# ArmRobot.net
KiCad netlist of a schematic drawn in EAGLE
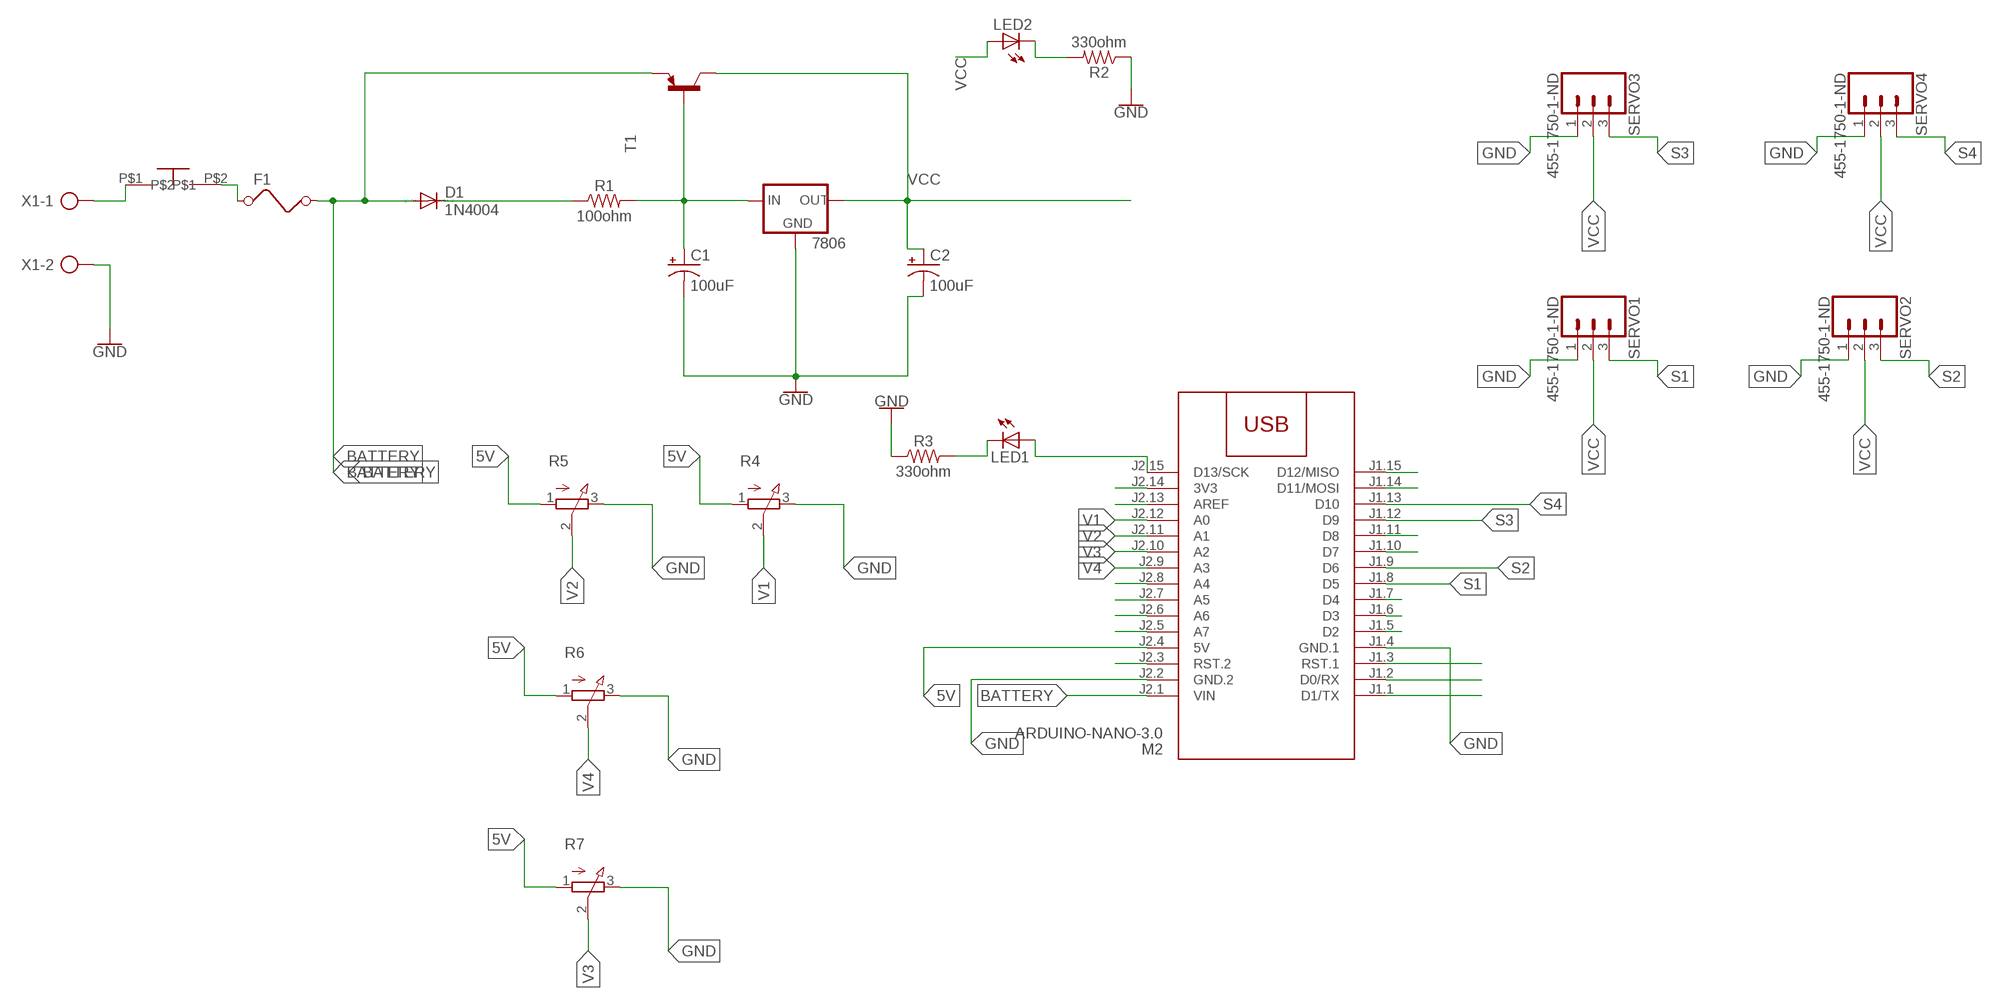
[diagram p0: schematic, sheet 1]

(export (version "E")
  (design (tool "Eeschema 10.0.6"))
  (components
    (comp (ref "7806")
      (value "78XXS")
      (footprint "eagle-import:78XXS")
      (libsource (lib "eagle-import") (part "78XXS"))
    )
    (comp (ref "C1")
      (value "100uF")
      (footprint "eagle-import:CPOL-RADIAL-2.5MM-6.5MM")
      (libsource (lib "eagle-import") (part "100UF-POLAR-RADIAL-2.5MM-25V-20%"))
    )
    (comp (ref "C2")
      (value "100uF")
      (footprint "eagle-import:CPOL-RADIAL-2.5MM-6.5MM")
      (libsource (lib "eagle-import") (part "100UF-POLAR-RADIAL-2.5MM-25V-20%"))
    )
    (comp (ref "D1")
      (value "1N4004")
      (footprint "eagle-import:DO41-10")
      (libsource (lib "eagle-import") (part "1N4004"))
    )
    (comp (ref "F1")
      (value "FUSE")
      (footprint "eagle-import:FUSE")
      (libsource (lib "eagle-import") (part "FUSE"))
    )
    (comp (ref "LED1")
      (value "LED3MM")
      (footprint "eagle-import:LED3MM")
      (libsource (lib "eagle-import") (part "LED3MM"))
    )
    (comp (ref "LED2")
      (value "LED3MM")
      (footprint "eagle-import:LED3MM")
      (libsource (lib "eagle-import") (part "LED3MM"))
    )
    (comp (ref "M2")
      (value "ARDUINO-NANO-3.0")
      (footprint "eagle-import:ARDUINO-NANO-3.0")
      (libsource (lib "eagle-import") (part "ARDUINO-NANO-3.0"))
    )
    (comp (ref "R1")
      (value "100ohm")
      (footprint "eagle-import:AXIAL-0.3")
      (libsource (lib "eagle-import") (part "10MOHM-HORIZ-1/4W-5%"))
    )
    (comp (ref "R2")
      (value "330ohm")
      (footprint "eagle-import:AXIAL-0.3")
      (libsource (lib "eagle-import") (part "10MOHM-HORIZ-1/4W-5%"))
    )
    (comp (ref "R3")
      (value "330ohm")
      (footprint "eagle-import:AXIAL-0.3")
      (libsource (lib "eagle-import") (part "10MOHM-HORIZ-1/4W-5%"))
    )
    (comp (ref "R4")
      (value "3RP/1610N")
      (footprint "eagle-import:3RP_1610N")
      (libsource (lib "eagle-import") (part "3RP/1610N"))
    )
    (comp (ref "R5")
      (value "3RP/1610N")
      (footprint "eagle-import:3RP_1610N")
      (libsource (lib "eagle-import") (part "3RP/1610N"))
    )
    (comp (ref "R6")
      (value "3RP/1610N")
      (footprint "eagle-import:3RP_1610N")
      (libsource (lib "eagle-import") (part "3RP/1610N"))
    )
    (comp (ref "R7")
      (value "3RP/1610N")
      (footprint "eagle-import:3RP_1610N")
      (libsource (lib "eagle-import") (part "3RP/1610N"))
    )
    (comp (ref "SERVO1")
      (value "455-1750-1-ND")
      (footprint "eagle-import:1X03")
      (libsource (lib "eagle-import") (part "CONN_03"))
    )
    (comp (ref "SERVO2")
      (value "455-1750-1-ND")
      (footprint "eagle-import:1X03")
      (libsource (lib "eagle-import") (part "CONN_03"))
    )
    (comp (ref "SERVO3")
      (value "455-1750-1-ND")
      (footprint "eagle-import:1X03")
      (libsource (lib "eagle-import") (part "CONN_03"))
    )
    (comp (ref "SERVO4")
      (value "455-1750-1-ND")
      (footprint "eagle-import:1X03")
      (libsource (lib "eagle-import") (part "CONN_03"))
    )
    (comp (ref "T1")
      (value "-PNP-TO220V")
      (footprint "eagle-import:TO220V")
      (libsource (lib "eagle-import") (part "-PNP-TO220V"))
    )
    (comp (ref "U$1")
      (value "ON_OFF")
      (footprint "eagle-import:ON_OFF")
      (libsource (lib "eagle-import") (part "ON_OFF"))
    )
    (comp (ref "X1")
      (value "AK500/2-H")
      (footprint "eagle-import:AK500_2-H")
      (libsource (lib "eagle-import") (part "AK500/2-H"))
    )
  )
  (nets
    (net (code "1") (name "5V") (class "Default")
      (node (ref "M2") (pin "J2.4") (pinfunction "5V_J2.4") (pintype "power_in"))
      (node (ref "R4") (pin "1") (pinfunction "A_1") (pintype "passive"))
      (node (ref "R5") (pin "1") (pinfunction "A_1") (pintype "passive"))
      (node (ref "R6") (pin "1") (pinfunction "A_1") (pintype "passive"))
      (node (ref "R7") (pin "1") (pinfunction "A_1") (pintype "passive"))
    )
    (net (code "2") (name "BATTERY") (class "Default")
      (node (ref "D1") (pin "A") (pinfunction "A_A") (pintype "passive"))
      (node (ref "F1") (pin "2") (pinfunction "2_2") (pintype "passive"))
      (node (ref "M2") (pin "J2.1") (pinfunction "VIN_J2.1") (pintype "power_in"))
      (node (ref "T1") (pin "3") (pinfunction "E_3") (pintype "passive"))
    )
    (net (code "3") (name "GND") (class "Default")
      (node (ref "7806") (pin "GND") (pinfunction "GND_GND") (pintype "input"))
      (node (ref "C1") (pin "2") (pinfunction "-_2") (pintype "passive"))
      (node (ref "C2") (pin "2") (pinfunction "-_2") (pintype "passive"))
      (node (ref "M2") (pin "J1.4") (pinfunction "GND.1_J1.4") (pintype "power_in"))
      (node (ref "M2") (pin "J2.2") (pinfunction "GND.2_J2.2") (pintype "power_in"))
      (node (ref "R2") (pin "P$1") (pinfunction "1_P$1") (pintype "passive"))
      (node (ref "R3") (pin "P$1") (pinfunction "1_P$1") (pintype "passive"))
      (node (ref "R4") (pin "3") (pinfunction "E_3") (pintype "passive"))
      (node (ref "R5") (pin "3") (pinfunction "E_3") (pintype "passive"))
      (node (ref "R6") (pin "3") (pinfunction "E_3") (pintype "passive"))
      (node (ref "R7") (pin "3") (pinfunction "E_3") (pintype "passive"))
      (node (ref "SERVO1") (pin "1") (pinfunction "1_1") (pintype "passive"))
      (node (ref "SERVO2") (pin "1") (pinfunction "1_1") (pintype "passive"))
      (node (ref "SERVO3") (pin "1") (pinfunction "1_1") (pintype "passive"))
      (node (ref "SERVO4") (pin "1") (pinfunction "1_1") (pintype "passive"))
      (node (ref "X1") (pin "2") (pinfunction "KL_2") (pintype "passive"))
    )
    (net (code "4") (name "Net-(C1-+)") (class "Default")
      (node (ref "7806") (pin "IN") (pinfunction "IN_IN") (pintype "input"))
      (node (ref "C1") (pin "1") (pinfunction "+_1") (pintype "passive"))
      (node (ref "R1") (pin "P$2") (pinfunction "2_P$2") (pintype "passive"))
      (node (ref "T1") (pin "1") (pinfunction "B_1") (pintype "passive"))
    )
    (net (code "5") (name "Net-(F1-Pad1)") (class "Default")
      (node (ref "F1") (pin "1") (pinfunction "1_1") (pintype "passive"))
      (node (ref "U$1") (pin "P$2") (pinfunction "P$2_P$2") (pintype "bidirectional"))
    )
    (net (code "6") (name "Net-(LED1-C)") (class "Default")
      (node (ref "LED1") (pin "K") (pinfunction "C_K") (pintype "passive"))
      (node (ref "R3") (pin "P$2") (pinfunction "2_P$2") (pintype "passive"))
    )
    (net (code "7") (name "Net-(LED2-C)") (class "Default")
      (node (ref "LED2") (pin "K") (pinfunction "C_K") (pintype "passive"))
      (node (ref "R2") (pin "P$2") (pinfunction "2_P$2") (pintype "passive"))
    )
    (net (code "8") (name "Net-(M2-D13{slash}SCK)") (class "Default")
      (node (ref "LED1") (pin "A") (pinfunction "A_A") (pintype "passive"))
      (node (ref "M2") (pin "J2.15") (pinfunction "D13/SCK_J2.15") (pintype "bidirectional"))
    )
    (net (code "9") (name "Net-(R1-1)") (class "Default")
      (node (ref "D1") (pin "C") (pinfunction "C_C") (pintype "passive"))
      (node (ref "R1") (pin "P$1") (pinfunction "1_P$1") (pintype "passive"))
    )
    (net (code "10") (name "Net-(X1A-KL)") (class "Default")
      (node (ref "U$1") (pin "P$1") (pinfunction "P$1_P$1") (pintype "bidirectional"))
      (node (ref "X1") (pin "1") (pinfunction "KL_1") (pintype "passive"))
    )
    (net (code "11") (name "S1") (class "Default")
      (node (ref "M2") (pin "J1.8") (pinfunction "D5_J1.8") (pintype "bidirectional"))
      (node (ref "SERVO1") (pin "3") (pinfunction "3_3") (pintype "passive"))
    )
    (net (code "12") (name "S2") (class "Default")
      (node (ref "M2") (pin "J1.9") (pinfunction "D6_J1.9") (pintype "bidirectional"))
      (node (ref "SERVO2") (pin "3") (pinfunction "3_3") (pintype "passive"))
    )
    (net (code "13") (name "S3") (class "Default")
      (node (ref "M2") (pin "J1.12") (pinfunction "D9_J1.12") (pintype "bidirectional"))
      (node (ref "SERVO3") (pin "3") (pinfunction "3_3") (pintype "passive"))
    )
    (net (code "14") (name "S4") (class "Default")
      (node (ref "M2") (pin "J1.13") (pinfunction "D10_J1.13") (pintype "bidirectional"))
      (node (ref "SERVO4") (pin "3") (pinfunction "3_3") (pintype "passive"))
    )
    (net (code "15") (name "V1") (class "Default")
      (node (ref "M2") (pin "J2.12") (pinfunction "A0_J2.12") (pintype "bidirectional"))
      (node (ref "R4") (pin "2") (pinfunction "S_2") (pintype "passive"))
    )
    (net (code "16") (name "V2") (class "Default")
      (node (ref "M2") (pin "J2.11") (pinfunction "A1_J2.11") (pintype "bidirectional"))
      (node (ref "R5") (pin "2") (pinfunction "S_2") (pintype "passive"))
    )
    (net (code "17") (name "V3") (class "Default")
      (node (ref "M2") (pin "J2.10") (pinfunction "A2_J2.10") (pintype "bidirectional"))
      (node (ref "R7") (pin "2") (pinfunction "S_2") (pintype "passive"))
    )
    (net (code "18") (name "V4") (class "Default")
      (node (ref "M2") (pin "J2.9") (pinfunction "A3_J2.9") (pintype "bidirectional"))
      (node (ref "R6") (pin "2") (pinfunction "S_2") (pintype "passive"))
    )
    (net (code "19") (name "VCC") (class "Default")
      (node (ref "7806") (pin "OUT") (pinfunction "OUT_OUT") (pintype "passive"))
      (node (ref "C2") (pin "1") (pinfunction "+_1") (pintype "passive"))
      (node (ref "LED2") (pin "A") (pinfunction "A_A") (pintype "passive"))
      (node (ref "SERVO1") (pin "2") (pinfunction "2_2") (pintype "passive"))
      (node (ref "SERVO2") (pin "2") (pinfunction "2_2") (pintype "passive"))
      (node (ref "SERVO3") (pin "2") (pinfunction "2_2") (pintype "passive"))
      (node (ref "SERVO4") (pin "2") (pinfunction "2_2") (pintype "passive"))
      (node (ref "T1") (pin "2") (pinfunction "C_2") (pintype "passive"))
    )
    (net (code "20") (name "unconnected-(M2-3V3-PadJ2.14)") (class "Default")
      (node (ref "M2") (pin "J2.14") (pinfunction "3V3_J2.14") (pintype "power_in"))
    )
    (net (code "21") (name "unconnected-(M2-A4-PadJ2.8)") (class "Default")
      (node (ref "M2") (pin "J2.8") (pinfunction "A4_J2.8") (pintype "bidirectional"))
    )
    (net (code "22") (name "unconnected-(M2-A5-PadJ2.7)") (class "Default")
      (node (ref "M2") (pin "J2.7") (pinfunction "A5_J2.7") (pintype "bidirectional"))
    )
    (net (code "23") (name "unconnected-(M2-A6-PadJ2.6)") (class "Default")
      (node (ref "M2") (pin "J2.6") (pinfunction "A6_J2.6") (pintype "bidirectional"))
    )
    (net (code "24") (name "unconnected-(M2-A7-PadJ2.5)") (class "Default")
      (node (ref "M2") (pin "J2.5") (pinfunction "A7_J2.5") (pintype "bidirectional"))
    )
    (net (code "25") (name "unconnected-(M2-AREF-PadJ2.13)") (class "Default")
      (node (ref "M2") (pin "J2.13") (pinfunction "AREF_J2.13") (pintype "bidirectional"))
    )
    (net (code "26") (name "unconnected-(M2-D0{slash}RX-PadJ1.2)") (class "Default")
      (node (ref "M2") (pin "J1.2") (pinfunction "D0/RX_J1.2") (pintype "bidirectional"))
    )
    (net (code "27") (name "unconnected-(M2-D1{slash}TX-PadJ1.1)") (class "Default")
      (node (ref "M2") (pin "J1.1") (pinfunction "D1/TX_J1.1") (pintype "bidirectional"))
    )
    (net (code "28") (name "unconnected-(M2-D2-PadJ1.5)") (class "Default")
      (node (ref "M2") (pin "J1.5") (pinfunction "D2_J1.5") (pintype "bidirectional"))
    )
    (net (code "29") (name "unconnected-(M2-D3-PadJ1.6)") (class "Default")
      (node (ref "M2") (pin "J1.6") (pinfunction "D3_J1.6") (pintype "bidirectional"))
    )
    (net (code "30") (name "unconnected-(M2-D4-PadJ1.7)") (class "Default")
      (node (ref "M2") (pin "J1.7") (pinfunction "D4_J1.7") (pintype "bidirectional"))
    )
    (net (code "31") (name "unconnected-(M2-D7-PadJ1.10)") (class "Default")
      (node (ref "M2") (pin "J1.10") (pinfunction "D7_J1.10") (pintype "bidirectional"))
    )
    (net (code "32") (name "unconnected-(M2-D8-PadJ1.11)") (class "Default")
      (node (ref "M2") (pin "J1.11") (pinfunction "D8_J1.11") (pintype "bidirectional"))
    )
    (net (code "33") (name "unconnected-(M2-D11{slash}MOSI-PadJ1.14)") (class "Default")
      (node (ref "M2") (pin "J1.14") (pinfunction "D11/MOSI_J1.14") (pintype "bidirectional"))
    )
    (net (code "34") (name "unconnected-(M2-D12{slash}MISO-PadJ1.15)") (class "Default")
      (node (ref "M2") (pin "J1.15") (pinfunction "D12/MISO_J1.15") (pintype "bidirectional"))
    )
    (net (code "35") (name "unconnected-(M2-RST.1-PadJ1.3)") (class "Default")
      (node (ref "M2") (pin "J1.3") (pinfunction "RST.1_J1.3") (pintype "bidirectional"))
    )
    (net (code "36") (name "unconnected-(M2-RST.2-PadJ2.3)") (class "Default")
      (node (ref "M2") (pin "J2.3") (pinfunction "RST.2_J2.3") (pintype "bidirectional"))
    )
  )
)
